# test.net
KiCad netlist of a schematic drawn in EAGLE
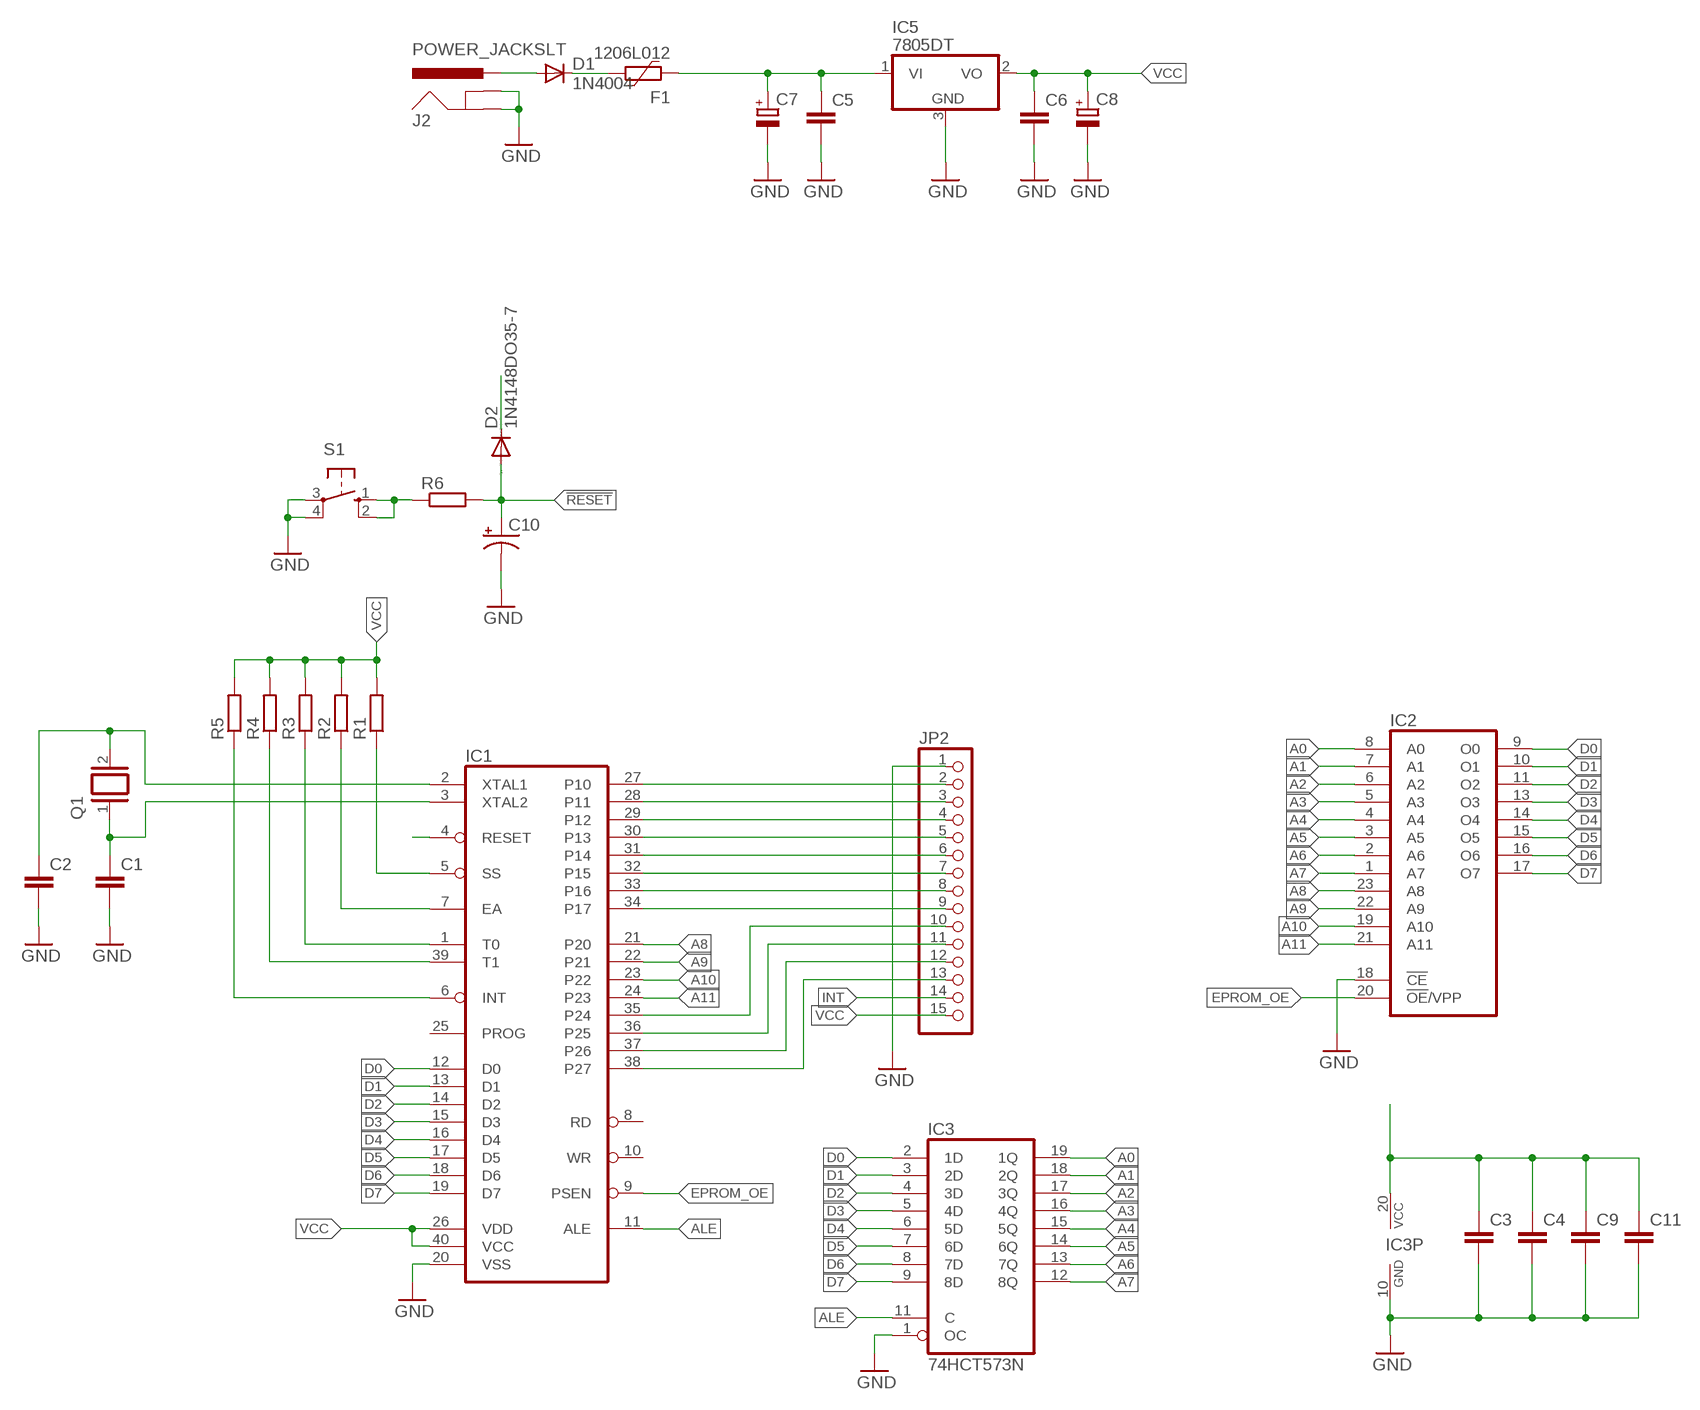
[diagram p0: schematic, sheet 1]

(export (version "E")
  (design (tool "Eeschema 10.0.6"))
  (components
    (comp (ref "C1")
      (value "C-EUC0603")
      (footprint "eagle-import:C0603")
      (libsource (lib "eagle-import") (part "C-EUC0603"))
    )
    (comp (ref "C2")
      (value "C-EUC0603")
      (footprint "eagle-import:C0603")
      (libsource (lib "eagle-import") (part "C-EUC0603"))
    )
    (comp (ref "C3")
      (value "C-EUC0603")
      (footprint "eagle-import:C0603")
      (libsource (lib "eagle-import") (part "C-EUC0603"))
    )
    (comp (ref "C4")
      (value "C-EUC0603")
      (footprint "eagle-import:C0603")
      (libsource (lib "eagle-import") (part "C-EUC0603"))
    )
    (comp (ref "C5")
      (value "C-EUC0603")
      (footprint "eagle-import:C0603")
      (libsource (lib "eagle-import") (part "C-EUC0603"))
    )
    (comp (ref "C6")
      (value "C-EUC0603")
      (footprint "eagle-import:C0603")
      (libsource (lib "eagle-import") (part "C-EUC0603"))
    )
    (comp (ref "C7")
      (value "CPOL-EUSMCB")
      (footprint "eagle-import:SMC_B")
      (libsource (lib "eagle-import") (part "CPOL-EUSMCB"))
    )
    (comp (ref "C8")
      (value "CPOL-EUSMCB")
      (footprint "eagle-import:SMC_B")
      (libsource (lib "eagle-import") (part "CPOL-EUSMCB"))
    )
    (comp (ref "C9")
      (value "C-EUC0603")
      (footprint "eagle-import:C0603")
      (libsource (lib "eagle-import") (part "C-EUC0603"))
    )
    (comp (ref "C10")
      (value "CPOL-USE2,5-6E")
      (footprint "eagle-import:E2,5-6E")
      (libsource (lib "eagle-import") (part "CPOL-USE2,5-6E"))
    )
    (comp (ref "C11")
      (value "C-EUC0603")
      (footprint "eagle-import:C0603")
      (libsource (lib "eagle-import") (part "C-EUC0603"))
    )
    (comp (ref "D1")
      (value "1N4004")
      (footprint "eagle-import:DO41-10")
      (libsource (lib "eagle-import") (part "1N4004"))
    )
    (comp (ref "D2")
      (value "1N4148DO35-7")
      (footprint "eagle-import:DO35-7")
      (libsource (lib "eagle-import") (part "1N4148DO35-7"))
    )
    (comp (ref "F1")
      (value "1206L012")
      (footprint "eagle-import:1206L")
      (fields (field (name "MF") "Littelfuse"))
      (libsource (lib "eagle-import") (part "?1206L012"))
    )
    (comp (ref "IC1")
      (value "8048")
      (footprint "eagle-import:DIL40")
      (libsource (lib "eagle-import") (part "8048"))
    )
    (comp (ref "IC2")
      (value "2732")
      (footprint "eagle-import:DIL24")
      (libsource (lib "eagle-import") (part "2732"))
    )
    (comp (ref "IC3")
      (value "74HCT573N")
      (footprint "eagle-import:DIL20")
      (libsource (lib "eagle-import") (part "74573NHCT"))
    )
    (comp (ref "IC5")
      (value "7805DT")
      (footprint "eagle-import:TO252")
      (libsource (lib "eagle-import") (part "78DT05"))
    )
    (comp (ref "J2")
      (value "POWER_JACKSLT")
      (footprint "eagle-import:POWER_JACK_SLOT")
      (libsource (lib "eagle-import") (part "POWER_JACKSLT"))
    )
    (comp (ref "JP2")
      (value "PINHD-1X15")
      (footprint "eagle-import:1X15")
      (libsource (lib "eagle-import") (part "PINHD-1X15"))
    )
    (comp (ref "Q1")
      (value "XTAL/S")
      (footprint "eagle-import:QS")
      (libsource (lib "eagle-import") (part "XTAL/S"))
    )
    (comp (ref "R1")
      (value "R-EU_R1206")
      (footprint "eagle-import:R1206")
      (libsource (lib "eagle-import") (part "R-EU_R1206"))
    )
    (comp (ref "R2")
      (value "R-EU_R1206")
      (footprint "eagle-import:R1206")
      (libsource (lib "eagle-import") (part "R-EU_R1206"))
    )
    (comp (ref "R3")
      (value "R-EU_R1206")
      (footprint "eagle-import:R1206")
      (libsource (lib "eagle-import") (part "R-EU_R1206"))
    )
    (comp (ref "R4")
      (value "R-EU_R0603")
      (footprint "eagle-import:R0603")
      (libsource (lib "eagle-import") (part "R-EU_R0603"))
    )
    (comp (ref "R5")
      (value "R-EU_R1206")
      (footprint "eagle-import:R1206")
      (libsource (lib "eagle-import") (part "R-EU_R1206"))
    )
    (comp (ref "R6")
      (value "R-EU_R0603")
      (footprint "eagle-import:R0603")
      (libsource (lib "eagle-import") (part "R-EU_R0603"))
    )
    (comp (ref "S1")
      (value "10-XX")
      (footprint "eagle-import:B3F-10XX")
      (fields (field (name "MPN") "B3F-1000"))
      (libsource (lib "eagle-import") (part "10-XX"))
    )
  )
  (nets
    (net (code "1") (name "/~{RESET}") (class "Default")
      (node (ref "C10") (pin "+") (pinfunction "+_+") (pintype "passive"))
      (node (ref "D2") (pin "A") (pinfunction "A_A") (pintype "passive"))
      (node (ref "IC1") (pin "4") (pinfunction "RESET_4") (pintype "input"))
      (node (ref "R6") (pin "2") (pinfunction "2_2") (pintype "passive"))
    )
    (net (code "2") (name "A0") (class "Default")
      (node (ref "IC2") (pin "8") (pinfunction "A0_8") (pintype "input"))
      (node (ref "IC3") (pin "19") (pinfunction "1Q_19") (pintype "tri_state"))
    )
    (net (code "3") (name "A1") (class "Default")
      (node (ref "IC2") (pin "7") (pinfunction "A1_7") (pintype "input"))
      (node (ref "IC3") (pin "18") (pinfunction "2Q_18") (pintype "tri_state"))
    )
    (net (code "4") (name "A2") (class "Default")
      (node (ref "IC2") (pin "6") (pinfunction "A2_6") (pintype "input"))
      (node (ref "IC3") (pin "17") (pinfunction "3Q_17") (pintype "tri_state"))
    )
    (net (code "5") (name "A3") (class "Default")
      (node (ref "IC2") (pin "5") (pinfunction "A3_5") (pintype "input"))
      (node (ref "IC3") (pin "16") (pinfunction "4Q_16") (pintype "tri_state"))
    )
    (net (code "6") (name "A4") (class "Default")
      (node (ref "IC2") (pin "4") (pinfunction "A4_4") (pintype "input"))
      (node (ref "IC3") (pin "15") (pinfunction "5Q_15") (pintype "tri_state"))
    )
    (net (code "7") (name "A5") (class "Default")
      (node (ref "IC2") (pin "3") (pinfunction "A5_3") (pintype "input"))
      (node (ref "IC3") (pin "14") (pinfunction "6Q_14") (pintype "tri_state"))
    )
    (net (code "8") (name "A6") (class "Default")
      (node (ref "IC2") (pin "2") (pinfunction "A6_2") (pintype "input"))
      (node (ref "IC3") (pin "13") (pinfunction "7Q_13") (pintype "tri_state"))
    )
    (net (code "9") (name "A7") (class "Default")
      (node (ref "IC2") (pin "1") (pinfunction "A7_1") (pintype "input"))
      (node (ref "IC3") (pin "12") (pinfunction "8Q_12") (pintype "tri_state"))
    )
    (net (code "10") (name "A8") (class "Default")
      (node (ref "IC1") (pin "21") (pinfunction "P20_21") (pintype "bidirectional"))
      (node (ref "IC2") (pin "23") (pinfunction "A8_23") (pintype "input"))
    )
    (net (code "11") (name "A9") (class "Default")
      (node (ref "IC1") (pin "22") (pinfunction "P21_22") (pintype "bidirectional"))
      (node (ref "IC2") (pin "22") (pinfunction "A9_22") (pintype "input"))
    )
    (net (code "12") (name "A10") (class "Default")
      (node (ref "IC1") (pin "23") (pinfunction "P22_23") (pintype "bidirectional"))
      (node (ref "IC2") (pin "19") (pinfunction "A10_19") (pintype "input"))
    )
    (net (code "13") (name "A11") (class "Default")
      (node (ref "IC1") (pin "24") (pinfunction "P23_24") (pintype "bidirectional"))
      (node (ref "IC2") (pin "21") (pinfunction "A11_21") (pintype "input"))
    )
    (net (code "14") (name "ALE") (class "Default")
      (node (ref "IC1") (pin "11") (pinfunction "ALE_11") (pintype "output"))
      (node (ref "IC3") (pin "11") (pinfunction "C_11") (pintype "input"))
    )
    (net (code "15") (name "D0") (class "Default")
      (node (ref "IC1") (pin "12") (pinfunction "D0_12") (pintype "bidirectional"))
      (node (ref "IC2") (pin "9") (pinfunction "O0_9") (pintype "tri_state"))
      (node (ref "IC3") (pin "2") (pinfunction "1D_2") (pintype "input"))
    )
    (net (code "16") (name "D1") (class "Default")
      (node (ref "IC1") (pin "13") (pinfunction "D1_13") (pintype "bidirectional"))
      (node (ref "IC2") (pin "10") (pinfunction "O1_10") (pintype "tri_state"))
      (node (ref "IC3") (pin "3") (pinfunction "2D_3") (pintype "input"))
    )
    (net (code "17") (name "D2") (class "Default")
      (node (ref "IC1") (pin "14") (pinfunction "D2_14") (pintype "bidirectional"))
      (node (ref "IC2") (pin "11") (pinfunction "O2_11") (pintype "tri_state"))
      (node (ref "IC3") (pin "4") (pinfunction "3D_4") (pintype "input"))
    )
    (net (code "18") (name "D3") (class "Default")
      (node (ref "IC1") (pin "15") (pinfunction "D3_15") (pintype "bidirectional"))
      (node (ref "IC2") (pin "13") (pinfunction "O3_13") (pintype "tri_state"))
      (node (ref "IC3") (pin "5") (pinfunction "4D_5") (pintype "input"))
    )
    (net (code "19") (name "D4") (class "Default")
      (node (ref "IC1") (pin "16") (pinfunction "D4_16") (pintype "bidirectional"))
      (node (ref "IC2") (pin "14") (pinfunction "O4_14") (pintype "tri_state"))
      (node (ref "IC3") (pin "6") (pinfunction "5D_6") (pintype "input"))
    )
    (net (code "20") (name "D5") (class "Default")
      (node (ref "IC1") (pin "17") (pinfunction "D5_17") (pintype "bidirectional"))
      (node (ref "IC2") (pin "15") (pinfunction "O5_15") (pintype "tri_state"))
      (node (ref "IC3") (pin "7") (pinfunction "6D_7") (pintype "input"))
    )
    (net (code "21") (name "D6") (class "Default")
      (node (ref "IC1") (pin "18") (pinfunction "D6_18") (pintype "bidirectional"))
      (node (ref "IC2") (pin "16") (pinfunction "O6_16") (pintype "tri_state"))
      (node (ref "IC3") (pin "8") (pinfunction "7D_8") (pintype "input"))
    )
    (net (code "22") (name "D7") (class "Default")
      (node (ref "IC1") (pin "19") (pinfunction "D7_19") (pintype "bidirectional"))
      (node (ref "IC2") (pin "17") (pinfunction "O7_17") (pintype "tri_state"))
      (node (ref "IC3") (pin "9") (pinfunction "8D_9") (pintype "input"))
    )
    (net (code "23") (name "EPROM_OE") (class "Default")
      (node (ref "IC1") (pin "9") (pinfunction "PSEN_9") (pintype "output"))
      (node (ref "IC2") (pin "20") (pinfunction "~{OE}/VPP_20") (pintype "input"))
    )
    (net (code "24") (name "GND") (class "Default")
      (node (ref "C1") (pin "2") (pinfunction "2_2") (pintype "passive"))
      (node (ref "C10") (pin "-") (pinfunction "-_-") (pintype "passive"))
      (node (ref "C11") (pin "2") (pinfunction "2_2") (pintype "passive"))
      (node (ref "C2") (pin "2") (pinfunction "2_2") (pintype "passive"))
      (node (ref "C3") (pin "2") (pinfunction "2_2") (pintype "passive"))
      (node (ref "C4") (pin "2") (pinfunction "2_2") (pintype "passive"))
      (node (ref "C5") (pin "2") (pinfunction "2_2") (pintype "passive"))
      (node (ref "C6") (pin "2") (pinfunction "2_2") (pintype "passive"))
      (node (ref "C7") (pin "-") (pinfunction "-_-") (pintype "passive"))
      (node (ref "C8") (pin "-") (pinfunction "-_-") (pintype "passive"))
      (node (ref "C9") (pin "2") (pinfunction "2_2") (pintype "passive"))
      (node (ref "IC1") (pin "20") (pinfunction "VSS_20") (pintype "power_in"))
      (node (ref "IC2") (pin "18") (pinfunction "~{CE}_18") (pintype "input"))
      (node (ref "IC3") (pin "1") (pinfunction "OC_1") (pintype "input"))
      (node (ref "IC3") (pin "10") (pinfunction "GND_10") (pintype "power_in"))
      (node (ref "IC5") (pin "3") (pinfunction "GND_3") (pintype "passive"))
      (node (ref "J2") (pin "GND@1") (pinfunction "GNDBREAK_GND@1") (pintype "bidirectional"))
      (node (ref "J2") (pin "GND@2") (pinfunction "GND_GND@2") (pintype "bidirectional"))
      (node (ref "JP2") (pin "1") (pinfunction "1_1") (pintype "passive"))
      (node (ref "S1") (pin "3") (pinfunction "P_3") (pintype "passive"))
      (node (ref "S1") (pin "4") (pinfunction "P1_4") (pintype "passive"))
    )
    (net (code "25") (name "INT") (class "Default")
      (node (ref "IC1") (pin "6") (pinfunction "INT_6") (pintype "input"))
      (node (ref "JP2") (pin "14") (pinfunction "14_14") (pintype "passive"))
      (node (ref "R5") (pin "1") (pinfunction "1_1") (pintype "passive"))
    )
    (net (code "26") (name "Net-(D1-PadA)") (class "Default")
      (node (ref "D1") (pin "A") (pinfunction "A_A") (pintype "passive"))
      (node (ref "J2") (pin "PWR") (pinfunction "PWR_PWR") (pintype "bidirectional"))
    )
    (net (code "27") (name "Net-(D1-PadC)") (class "Default")
      (node (ref "D1") (pin "C") (pinfunction "C_C") (pintype "passive"))
      (node (ref "F1") (pin "1") (pinfunction "1_1") (pintype "passive"))
    )
    (net (code "28") (name "Net-(IC1-EA)") (class "Default")
      (node (ref "IC1") (pin "7") (pinfunction "EA_7") (pintype "input"))
      (node (ref "R2") (pin "1") (pinfunction "1_1") (pintype "passive"))
    )
    (net (code "29") (name "Net-(IC1-P10)") (class "Default")
      (node (ref "IC1") (pin "27") (pinfunction "P10_27") (pintype "bidirectional"))
      (node (ref "JP2") (pin "2") (pinfunction "2_2") (pintype "passive"))
    )
    (net (code "30") (name "Net-(IC1-P11)") (class "Default")
      (node (ref "IC1") (pin "28") (pinfunction "P11_28") (pintype "bidirectional"))
      (node (ref "JP2") (pin "3") (pinfunction "3_3") (pintype "passive"))
    )
    (net (code "31") (name "Net-(IC1-P12)") (class "Default")
      (node (ref "IC1") (pin "29") (pinfunction "P12_29") (pintype "bidirectional"))
      (node (ref "JP2") (pin "4") (pinfunction "4_4") (pintype "passive"))
    )
    (net (code "32") (name "Net-(IC1-P13)") (class "Default")
      (node (ref "IC1") (pin "30") (pinfunction "P13_30") (pintype "bidirectional"))
      (node (ref "JP2") (pin "5") (pinfunction "5_5") (pintype "passive"))
    )
    (net (code "33") (name "Net-(IC1-P14)") (class "Default")
      (node (ref "IC1") (pin "31") (pinfunction "P14_31") (pintype "bidirectional"))
      (node (ref "JP2") (pin "6") (pinfunction "6_6") (pintype "passive"))
    )
    (net (code "34") (name "Net-(IC1-P15)") (class "Default")
      (node (ref "IC1") (pin "32") (pinfunction "P15_32") (pintype "bidirectional"))
      (node (ref "JP2") (pin "7") (pinfunction "7_7") (pintype "passive"))
    )
    (net (code "35") (name "Net-(IC1-P16)") (class "Default")
      (node (ref "IC1") (pin "33") (pinfunction "P16_33") (pintype "bidirectional"))
      (node (ref "JP2") (pin "8") (pinfunction "8_8") (pintype "passive"))
    )
    (net (code "36") (name "Net-(IC1-P17)") (class "Default")
      (node (ref "IC1") (pin "34") (pinfunction "P17_34") (pintype "bidirectional"))
      (node (ref "JP2") (pin "9") (pinfunction "9_9") (pintype "passive"))
    )
    (net (code "37") (name "Net-(IC1-P24)") (class "Default")
      (node (ref "IC1") (pin "35") (pinfunction "P24_35") (pintype "bidirectional"))
      (node (ref "JP2") (pin "10") (pinfunction "10_10") (pintype "passive"))
    )
    (net (code "38") (name "Net-(IC1-P25)") (class "Default")
      (node (ref "IC1") (pin "36") (pinfunction "P25_36") (pintype "bidirectional"))
      (node (ref "JP2") (pin "11") (pinfunction "11_11") (pintype "passive"))
    )
    (net (code "39") (name "Net-(IC1-P26)") (class "Default")
      (node (ref "IC1") (pin "37") (pinfunction "P26_37") (pintype "bidirectional"))
      (node (ref "JP2") (pin "12") (pinfunction "12_12") (pintype "passive"))
    )
    (net (code "40") (name "Net-(IC1-P27)") (class "Default")
      (node (ref "IC1") (pin "38") (pinfunction "P27_38") (pintype "bidirectional"))
      (node (ref "JP2") (pin "13") (pinfunction "13_13") (pintype "passive"))
    )
    (net (code "41") (name "Net-(IC1-SS)") (class "Default")
      (node (ref "IC1") (pin "5") (pinfunction "SS_5") (pintype "input"))
      (node (ref "R1") (pin "1") (pinfunction "1_1") (pintype "passive"))
    )
    (net (code "42") (name "Net-(IC1-T0)") (class "Default")
      (node (ref "IC1") (pin "1") (pinfunction "T0_1") (pintype "input"))
      (node (ref "R3") (pin "1") (pinfunction "1_1") (pintype "passive"))
    )
    (net (code "43") (name "Net-(IC1-T1)") (class "Default")
      (node (ref "IC1") (pin "39") (pinfunction "T1_39") (pintype "input"))
      (node (ref "R4") (pin "1") (pinfunction "1_1") (pintype "passive"))
    )
    (net (code "44") (name "Net-(IC1-XTAL1)") (class "Default")
      (node (ref "C2") (pin "1") (pinfunction "1_1") (pintype "passive"))
      (node (ref "IC1") (pin "2") (pinfunction "XTAL1_2") (pintype "input"))
      (node (ref "Q1") (pin "2") (pinfunction "2_2") (pintype "passive"))
    )
    (net (code "45") (name "Net-(IC1-XTAL2)") (class "Default")
      (node (ref "C1") (pin "1") (pinfunction "1_1") (pintype "passive"))
      (node (ref "IC1") (pin "3") (pinfunction "XTAL2_3") (pintype "output"))
      (node (ref "Q1") (pin "1") (pinfunction "1_1") (pintype "passive"))
    )
    (net (code "46") (name "Net-(IC5-VI)") (class "Default")
      (node (ref "C5") (pin "1") (pinfunction "1_1") (pintype "passive"))
      (node (ref "C7") (pin "+") (pinfunction "+_+") (pintype "passive"))
      (node (ref "F1") (pin "2") (pinfunction "2_2") (pintype "passive"))
      (node (ref "IC5") (pin "1") (pinfunction "VI_1") (pintype "input"))
    )
    (net (code "47") (name "Net-(S1-S)") (class "Default")
      (node (ref "R6") (pin "1") (pinfunction "1_1") (pintype "passive"))
      (node (ref "S1") (pin "1") (pinfunction "S_1") (pintype "passive"))
      (node (ref "S1") (pin "2") (pinfunction "S1_2") (pintype "passive"))
    )
    (net (code "48") (name "VCC") (class "Default")
      (node (ref "C11") (pin "1") (pinfunction "1_1") (pintype "passive"))
      (node (ref "C3") (pin "1") (pinfunction "1_1") (pintype "passive"))
      (node (ref "C4") (pin "1") (pinfunction "1_1") (pintype "passive"))
      (node (ref "C6") (pin "1") (pinfunction "1_1") (pintype "passive"))
      (node (ref "C8") (pin "+") (pinfunction "+_+") (pintype "passive"))
      (node (ref "C9") (pin "1") (pinfunction "1_1") (pintype "passive"))
      (node (ref "D2") (pin "C") (pinfunction "C_C") (pintype "passive"))
      (node (ref "IC1") (pin "26") (pinfunction "VDD_26") (pintype "power_in"))
      (node (ref "IC1") (pin "40") (pinfunction "VCC_40") (pintype "power_in"))
      (node (ref "IC3") (pin "20") (pinfunction "VCC_20") (pintype "power_in"))
      (node (ref "IC5") (pin "2") (pinfunction "VO_2") (pintype "passive"))
      (node (ref "JP2") (pin "15") (pinfunction "15_15") (pintype "passive"))
      (node (ref "R1") (pin "2") (pinfunction "2_2") (pintype "passive"))
      (node (ref "R2") (pin "2") (pinfunction "2_2") (pintype "passive"))
      (node (ref "R3") (pin "2") (pinfunction "2_2") (pintype "passive"))
      (node (ref "R4") (pin "2") (pinfunction "2_2") (pintype "passive"))
      (node (ref "R5") (pin "2") (pinfunction "2_2") (pintype "passive"))
    )
    (net (code "49") (name "unconnected-(IC1-PROG-Pad25)") (class "Default")
      (node (ref "IC1") (pin "25") (pinfunction "PROG_25") (pintype "input"))
    )
    (net (code "50") (name "unconnected-(IC1-RD-Pad8)") (class "Default")
      (node (ref "IC1") (pin "8") (pinfunction "RD_8") (pintype "output"))
    )
    (net (code "51") (name "unconnected-(IC1-WR-Pad10)") (class "Default")
      (node (ref "IC1") (pin "10") (pinfunction "WR_10") (pintype "output"))
    )
  )
)
